# CD2840ADX-V2_2.net
KiCad netlist of a schematic drawn in Altium Designer
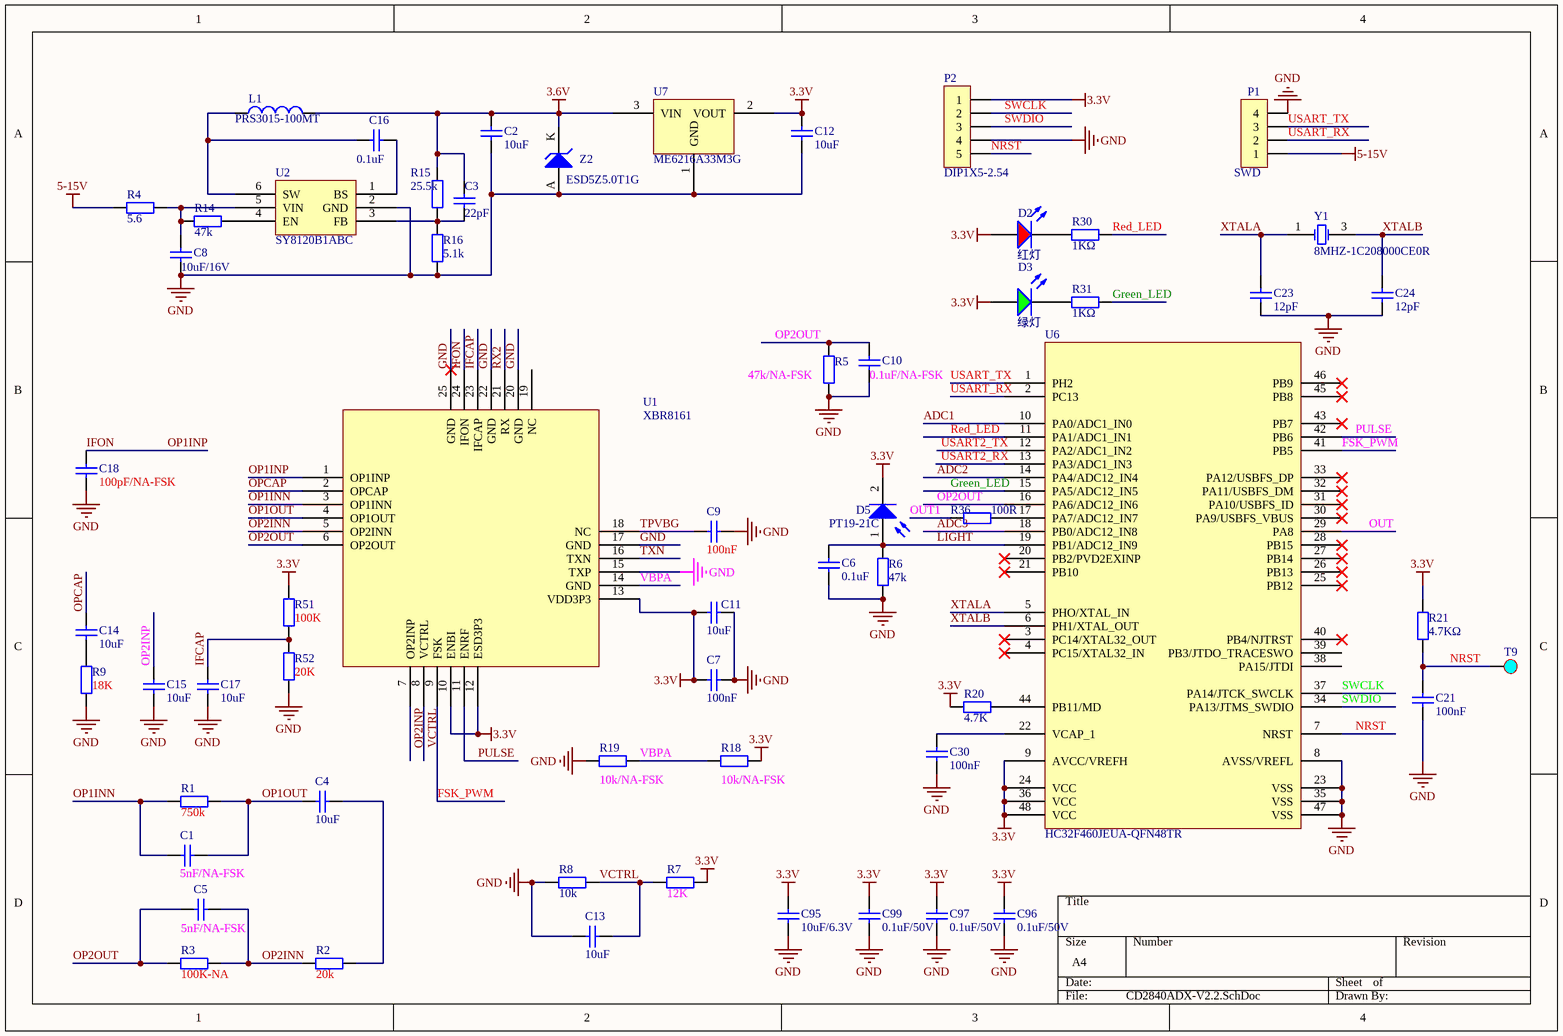
[diagram p0: CD2840ADX-V2.2.SchDoc]

(export (version "E")
  (design (tool "Eeschema 10.0.6"))
  (components
    (comp (ref "C1")
      (value "5nF/NA-FSK")
      (footprint "C0402")
      (description "Capacitor")
      (fields (field (name "PUBLISHER") "Altium Limited"))
      (libsource (lib "Miscellaneous Devices") (part "Cap"))
    )
    (comp (ref "C2")
      (value "10uF")
      (footprint "C0402")
      (description "Capacitor")
      (fields (field (name "PUBLISHER") "Altium Limited"))
      (libsource (lib "Miscellaneous Devices") (part "Cap"))
    )
    (comp (ref "C3")
      (value "22pF")
      (footprint "C0402")
      (description "Capacitor")
      (fields (field (name "PUBLISHER") "Altium Limited"))
      (libsource (lib "Miscellaneous Devices") (part "Cap"))
    )
    (comp (ref "C4")
      (value "10uF")
      (footprint "C0402")
      (description "Capacitor")
      (fields (field (name "PUBLISHER") "Altium Limited"))
      (libsource (lib "Miscellaneous Devices") (part "Cap"))
    )
    (comp (ref "C5")
      (value "5nF/NA-FSK")
      (footprint "C0402")
      (description "Capacitor")
      (fields (field (name "PUBLISHER") "Altium Limited"))
      (libsource (lib "Miscellaneous Devices") (part "Cap"))
    )
    (comp (ref "C6")
      (value "0.1uF")
      (footprint "C0402")
      (description "Capacitor")
      (fields (field (name "PUBLISHER") "Altium Limited"))
      (libsource (lib "Miscellaneous Devices") (part "Cap"))
    )
    (comp (ref "C7")
      (value "100nF")
      (footprint "C0402")
      (description "Capacitor")
      (fields (field (name "PUBLISHER") "Altium Limited"))
      (libsource (lib "Miscellaneous Devices") (part "Cap"))
    )
    (comp (ref "C8")
      (value "10uF/16V")
      (footprint "C0603")
      (description "Capacitor")
      (fields (field (name "PUBLISHER") "Altium Limited"))
      (libsource (lib "Miscellaneous Devices") (part "Cap"))
    )
    (comp (ref "C9")
      (value "100nF")
      (footprint "C0402")
      (description "Capacitor")
      (fields (field (name "PUBLISHER") "Altium Limited"))
      (libsource (lib "Miscellaneous Devices") (part "Cap"))
    )
    (comp (ref "C10")
      (value "0.1uF/NA-FSK")
      (footprint "C0402")
      (description "Capacitor")
      (fields (field (name "PUBLISHER") "Altium Limited"))
      (libsource (lib "Miscellaneous Devices") (part "Cap"))
    )
    (comp (ref "C11")
      (value "10uF")
      (footprint "C0402")
      (description "Capacitor")
      (fields (field (name "PUBLISHER") "Altium Limited"))
      (libsource (lib "Miscellaneous Devices") (part "Cap"))
    )
    (comp (ref "C12")
      (value "10uF")
      (footprint "C0402")
      (description "Capacitor")
      (fields (field (name "PUBLISHER") "Altium Limited"))
      (libsource (lib "Miscellaneous Devices") (part "Cap"))
    )
    (comp (ref "C13")
      (value "10uF")
      (footprint "C0402")
      (description "Capacitor")
      (fields (field (name "PUBLISHER") "Altium Limited"))
      (libsource (lib "Miscellaneous Devices") (part "Cap"))
    )
    (comp (ref "C14")
      (value "10uF")
      (footprint "C0402")
      (description "Capacitor")
      (fields (field (name "PUBLISHER") "Altium Limited"))
      (libsource (lib "Miscellaneous Devices") (part "Cap"))
    )
    (comp (ref "C15")
      (value "10uF")
      (footprint "C0402")
      (description "Capacitor")
      (fields (field (name "PUBLISHER") "Altium Limited"))
      (libsource (lib "Miscellaneous Devices") (part "Cap"))
    )
    (comp (ref "C16")
      (value "0.1uF")
      (footprint "C0402")
      (description "Capacitor")
      (fields (field (name "PUBLISHER") "Altium Limited"))
      (libsource (lib "Miscellaneous Devices") (part "Cap"))
    )
    (comp (ref "C17")
      (value "10uF")
      (footprint "C0402")
      (description "Capacitor")
      (fields (field (name "PUBLISHER") "Altium Limited"))
      (libsource (lib "Miscellaneous Devices") (part "Cap"))
    )
    (comp (ref "C18")
      (value "100pF/NA-FSK")
      (footprint "C0402")
      (description "Capacitor")
      (fields (field (name "PUBLISHER") "Altium Limited"))
      (libsource (lib "Miscellaneous Devices") (part "Cap"))
    )
    (comp (ref "C21")
      (value "100nF")
      (footprint "C0402")
      (description "贴片电容")
      (libsource (lib "Miscellaneous Devices LC") (part "0402 100nF (104) 10% 16V"))
    )
    (comp (ref "C23")
      (value "12pF")
      (footprint "C0402")
      (description "贴片电容")
      (libsource (lib "Cap") (part "0402 22pF (220) 5% 50V"))
    )
    (comp (ref "C24")
      (value "12pF")
      (footprint "C0402")
      (description "贴片电容")
      (libsource (lib "Cap") (part "0402 22pF (220) 5% 50V"))
    )
    (comp (ref "C30")
      (value "100nF")
      (footprint "C0402")
      (description "Capacitor")
      (fields (field (name "PUBLISHER") "Altium Limited"))
      (libsource (lib "Miscellaneous Devices") (part "Cap"))
    )
    (comp (ref "C95")
      (value "10uF/6.3V")
      (footprint "C0402")
      (description "贴片电容")
      (libsource (lib "Cap") (part "0402 2.2nF (222) 10% 50V"))
    )
    (comp (ref "C96")
      (value "0.1uF/50V")
      (footprint "C0402")
      (description "贴片电容")
      (libsource (lib "Cap") (part "0402 2.2nF (222) 10% 50V"))
    )
    (comp (ref "C97")
      (value "0.1uF/50V")
      (footprint "C0402")
      (description "贴片电容")
      (libsource (lib "Cap") (part "0402 2.2nF (222) 10% 50V"))
    )
    (comp (ref "C99")
      (value "0.1uF/50V")
      (footprint "C0402")
      (description "贴片电容")
      (libsource (lib "Cap") (part "0402 2.2nF (222) 10% 50V"))
    )
    (comp (ref "D2")
      (value "红灯")
      (footprint "LC-0603_LED_S1")
      (description "发光二极管")
      (libsource (lib "Miscellaneous Devices LC") (part "0603 红灯"))
    )
    (comp (ref "D3")
      (value "绿灯")
      (footprint "LC-0603_LED_S1")
      (description "发光二极管")
      (libsource (lib "30x35雷达微动底板V0.2") (part "0603 红灯"))
    )
    (comp (ref "D5")
      (value "PT19-21C")
      (footprint "LED-0603")
      (description "Photosensitive Diode")
      (fields (field (name "PUBLISHER") "Altium Limited"))
      (libsource (lib "Miscellaneous Devices") (part "Photo Sen"))
    )
    (comp (ref "L1")
      (value "PRS3015-100MT")
      (footprint "PRS3015")
      (description "Inductor")
      (fields (field (name "PUBLISHER") "Altium Limited"))
      (libsource (lib "Miscellaneous Devices") (part "Inductor"))
    )
    (comp (ref "P1")
      (value "SWD")
      (footprint "XH2.54mm")
      (description "4P接插件")
      (libsource (lib "STM32F407_CORE_BOARD") (part "Header 4"))
    )
    (comp (ref "P2")
      (value "DIP1X5-2.54")
      (footprint "DIP1X5-2.54")
      (description "4P接插件")
      (libsource (lib "CD2840ADX-V2.1") (part "Header 4"))
    )
    (comp (ref "R1")
      (value "750k")
      (footprint "R0402")
      (description "Resistor")
      (fields (field (name "PUBLISHER") "Altium Limited"))
      (libsource (lib "") (part "Res2_4"))
    )
    (comp (ref "R2")
      (value "20k")
      (footprint "R0402")
      (description "Resistor")
      (fields (field (name "PUBLISHER") "Altium Limited"))
      (libsource (lib "Miscellaneous Devices") (part "Res2"))
    )
    (comp (ref "R3")
      (value "100K-NA")
      (footprint "R0402")
      (description "Resistor")
      (fields (field (name "PUBLISHER") "Altium Limited"))
      (libsource (lib "Miscellaneous Devices") (part "Res2"))
    )
    (comp (ref "R4")
      (value "5.6")
      (footprint "R0402")
      (description "Resistor")
      (fields (field (name "PUBLISHER") "Altium Limited"))
      (libsource (lib "") (part "Res2_3"))
    )
    (comp (ref "R5")
      (value "47k/NA-FSK")
      (footprint "R0402")
      (description "Resistor")
      (fields (field (name "PUBLISHER") "Altium Limited"))
      (libsource (lib "") (part "Res2_1"))
    )
    (comp (ref "R6")
      (value "47k")
      (footprint "R0402")
      (description "Resistor")
      (fields (field (name "PUBLISHER") "Altium Limited"))
      (libsource (lib "") (part "Res2_1"))
    )
    (comp (ref "R7")
      (value "12K")
      (footprint "R0402")
      (description "Resistor")
      (fields (field (name "PUBLISHER") "Altium Limited"))
      (libsource (lib "Miscellaneous Devices") (part "Res2"))
    )
    (comp (ref "R8")
      (value "10k")
      (footprint "R0402")
      (description "Resistor")
      (fields (field (name "PUBLISHER") "Altium Limited"))
      (libsource (lib "Miscellaneous Devices") (part "Res2"))
    )
    (comp (ref "R9")
      (value "18K")
      (footprint "R0402")
      (description "Resistor")
      (fields (field (name "PUBLISHER") "Altium Limited"))
      (libsource (lib "") (part "Res2_1"))
    )
    (comp (ref "R14")
      (value "47k")
      (footprint "R0402")
      (description "Resistor")
      (fields (field (name "PUBLISHER") "Altium Limited"))
      (libsource (lib "Miscellaneous Devices") (part "Res2"))
    )
    (comp (ref "R15")
      (value "25.5k")
      (footprint "R0402")
      (description "Resistor")
      (fields (field (name "PUBLISHER") "Altium Limited"))
      (libsource (lib "") (part "Res2_2"))
    )
    (comp (ref "R16")
      (value "5.1k")
      (footprint "R0402")
      (description "Resistor")
      (fields (field (name "PUBLISHER") "Altium Limited"))
      (libsource (lib "") (part "Res2_2"))
    )
    (comp (ref "R18")
      (value "10k/NA-FSK")
      (footprint "R0402")
      (description "Resistor")
      (fields (field (name "PUBLISHER") "Altium Limited"))
      (libsource (lib "Miscellaneous Devices") (part "Res2"))
    )
    (comp (ref "R19")
      (value "10k/NA-FSK")
      (footprint "R0402")
      (description "Resistor")
      (fields (field (name "PUBLISHER") "Altium Limited"))
      (libsource (lib "Miscellaneous Devices") (part "Res2"))
    )
    (comp (ref "R20")
      (value "4.7K")
      (footprint "R0402")
      (description "Resistor")
      (fields (field (name "PUBLISHER") "Altium Limited"))
      (libsource (lib "") (part "Res2_4"))
    )
    (comp (ref "R21")
      (value "4.7KΩ")
      (footprint "R0402")
      (description "贴片电阻")
      (libsource (lib "") (part "0402 4.7KΩ (4701) 1%_1"))
    )
    (comp (ref "R30")
      (value "1KΩ")
      (footprint "R0402")
      (description "贴片电阻")
      (libsource (lib "Miscellaneous Devices LC") (part "0402 1KΩ (1001) 1%"))
    )
    (comp (ref "R31")
      (value "1KΩ")
      (footprint "R0402")
      (description "贴片电阻")
      (libsource (lib "Miscellaneous Devices LC") (part "0402 1KΩ (1001) 1%"))
    )
    (comp (ref "R36")
      (value "100R")
      (footprint "R0402")
      (description "贴片电阻")
      (libsource (lib "Miscellaneous Devices LC") (part "0402 4.7KΩ (4701) 1%"))
    )
    (comp (ref "R51")
      (value "100K")
      (footprint "R0402")
      (description "Resistor")
      (fields (field (name "PUBLISHER") "Altium Limited"))
      (libsource (lib "") (part "Res2_1"))
    )
    (comp (ref "R52")
      (value "20K")
      (footprint "R0402")
      (description "Resistor")
      (fields (field (name "PUBLISHER") "Altium Limited"))
      (libsource (lib "") (part "Res2_1"))
    )
    (comp (ref "T9")
      (value "~")
      (footprint "TestPoints")
      (description "TestPoints")
      (libsource (lib "标准原理图库（特种板）") (part "TestPoints"))
    )
    (comp (ref "U1")
      (value "XBR8161")
      (footprint "QFN24")
      (libsource (lib "altium-import") (part "root_0_XBR8161_"))
    )
    (comp (ref "U2") (value "SY8120B1ABC") (footprint "SOT-23-6") (libsource (lib "Schlib1") (part "H9108")))
    (comp (ref "U6")
      (value "HC32F460JEUA-QFN48TR")
      (footprint "QFN48-5X5mm")
      (libsource (lib "LD-ShouShi-Module-V1.0") (part "HC32F460JETA-LQFP48"))
    )
    (comp (ref "U7")
      (value "ME6216A33M3G")
      (footprint "SOT-23-L")
      (libsource (lib "Schlib1") (part "SSP6206"))
    )
    (comp (ref "Y1")
      (value "8MHZ-1C208000CE0R")
      (footprint "OSC-SMD_3225")
      (description "贴片晶振")
      (libsource (lib "CrystalOscillator") (part "SMD-3225_4P  25MHZ 12PF 10PPM"))
    )
    (comp (ref "Z2")
      (value "ESD5Z5.0T1G")
      (footprint "SOD323")
      (description "Zener Diode")
      (fields (field (name "PUBLISHER") "Altium Limited"))
      (libsource (lib "Miscellaneous Devices") (part "D Zener"))
    )
  )
  (nets
    (net (code "1") (name "/ADC1") (class "Default")
      (node (ref "U6") (pin "10") (pinfunction "PA0/ADC1_IN0_10") (pintype "passive"))
    )
    (net (code "2") (name "/ADC2") (class "Default")
      (node (ref "U6") (pin "14") (pinfunction "PA4/ADC12_IN4_14") (pintype "passive"))
    )
    (net (code "3") (name "/ADC3") (class "Default")
      (node (ref "U6") (pin "18") (pinfunction "PB0/ADC12_IN8_18") (pintype "passive"))
    )
    (net (code "4") (name "/FSK_PWM") (class "Default")
      (node (ref "U1") (pin "9") (pinfunction "FSK_9") (pintype "passive"))
      (node (ref "U6") (pin "41") (pinfunction "PB5_41") (pintype "passive"))
    )
    (net (code "5") (name "/Green_LED") (class "Default")
      (node (ref "R31") (pin "1") (pinfunction "1_1") (pintype "passive"))
      (node (ref "U6") (pin "15") (pinfunction "PA5/ADC12_IN5_15") (pintype "passive"))
    )
    (net (code "6") (name "/IFCAP") (class "Default")
      (node (ref "C17") (pin "2") (pinfunction "2_2") (pintype "passive"))
      (node (ref "R51") (pin "2") (pinfunction "2_2") (pintype "passive"))
      (node (ref "R52") (pin "1") (pinfunction "1_1") (pintype "passive"))
      (node (ref "U1") (pin "23") (pinfunction "IFCAP_23") (pintype "passive"))
    )
    (net (code "7") (name "/IFON") (class "Default")
      (node (ref "C18") (pin "2") (pinfunction "2_2") (pintype "passive"))
      (node (ref "U1") (pin "1") (pinfunction "OP1INP_1") (pintype "passive"))
      (node (ref "U1") (pin "24") (pinfunction "IFON_24") (pintype "passive"))
    )
    (net (code "8") (name "/LIGHT") (class "Default")
      (node (ref "C6") (pin "1") (pinfunction "1_1") (pintype "passive"))
      (node (ref "D5") (pin "1") (pinfunction "A_1") (pintype "passive"))
      (node (ref "R6") (pin "1") (pinfunction "1_1") (pintype "passive"))
      (node (ref "U6") (pin "19") (pinfunction "PB1/ADC12_IN9_19") (pintype "passive"))
    )
    (net (code "9") (name "/NRST") (class "Default")
      (node (ref "C21") (pin "2") (pinfunction "2_2") (pintype "passive"))
      (node (ref "P2") (pin "5") (pinfunction "5_5") (pintype "passive"))
      (node (ref "R21") (pin "1") (pinfunction "1_1") (pintype "passive"))
      (node (ref "T9") (pin "1") (pinfunction "1_1") (pintype "passive"))
      (node (ref "U6") (pin "7") (pinfunction "NRST_7") (pintype "passive"))
    )
    (net (code "10") (name "/OP1INN") (class "Default")
      (node (ref "C1") (pin "2") (pinfunction "2_2") (pintype "passive"))
      (node (ref "R1") (pin "1") (pinfunction "1_1") (pintype "passive"))
      (node (ref "U1") (pin "3") (pinfunction "OP1INN_3") (pintype "passive"))
    )
    (net (code "11") (name "/OP1OUT") (class "Default")
      (node (ref "C1") (pin "1") (pinfunction "1_1") (pintype "passive"))
      (node (ref "C4") (pin "2") (pinfunction "2_2") (pintype "passive"))
      (node (ref "R1") (pin "2") (pinfunction "2_2") (pintype "passive"))
      (node (ref "U1") (pin "4") (pinfunction "OP1OUT_4") (pintype "passive"))
    )
    (net (code "12") (name "/OP2INN") (class "Default")
      (node (ref "C5") (pin "2") (pinfunction "2_2") (pintype "passive"))
      (node (ref "R2") (pin "2") (pinfunction "2_2") (pintype "passive"))
      (node (ref "R3") (pin "1") (pinfunction "1_1") (pintype "passive"))
      (node (ref "U1") (pin "5") (pinfunction "OP2INN_5") (pintype "passive"))
    )
    (net (code "13") (name "/OP2INP") (class "Default")
      (node (ref "C15") (pin "1") (pinfunction "1_1") (pintype "passive"))
      (node (ref "U1") (pin "7") (pinfunction "OP2INP_7") (pintype "passive"))
    )
    (net (code "14") (name "/OP2OUT") (class "Default")
      (node (ref "C10") (pin "1") (pinfunction "1_1") (pintype "passive"))
      (node (ref "C5") (pin "1") (pinfunction "1_1") (pintype "passive"))
      (node (ref "R3") (pin "2") (pinfunction "2_2") (pintype "passive"))
      (node (ref "R5") (pin "1") (pinfunction "1_1") (pintype "passive"))
      (node (ref "U1") (pin "6") (pinfunction "OP2OUT_6") (pintype "passive"))
      (node (ref "U6") (pin "16") (pinfunction "PA6/ADC12_IN6_16") (pintype "passive"))
    )
    (net (code "15") (name "/OPCAP") (class "Default")
      (node (ref "C14") (pin "2") (pinfunction "2_2") (pintype "passive"))
      (node (ref "U1") (pin "2") (pinfunction "OPCAP_2") (pintype "passive"))
    )
    (net (code "16") (name "/OUT") (class "Default")
      (node (ref "U6") (pin "29") (pinfunction "PA8_29") (pintype "passive"))
    )
    (net (code "17") (name "/OUT1") (class "Default")
      (node (ref "R36") (pin "2") (pinfunction "2_2") (pintype "passive"))
    )
    (net (code "18") (name "/PULSE") (class "Default")
      (node (ref "U1") (pin "11") (pinfunction "ENRF_11") (pintype "passive"))
      (node (ref "U6") (pin "42") (pinfunction "PB6_42") (pintype "passive"))
    )
    (net (code "19") (name "/RX2") (class "Default")
      (node (ref "U1") (pin "21") (pinfunction "RX_21") (pintype "passive"))
    )
    (net (code "20") (name "/Red_LED") (class "Default")
      (node (ref "R30") (pin "1") (pinfunction "1_1") (pintype "passive"))
      (node (ref "U6") (pin "11") (pinfunction "PA1/ADC1_IN1_11") (pintype "passive"))
    )
    (net (code "21") (name "/SWCLK") (class "Default")
      (node (ref "P2") (pin "2") (pinfunction "2_2") (pintype "passive"))
      (node (ref "U6") (pin "37") (pinfunction "PA14/JTCK_SWCLK_37") (pintype "passive"))
    )
    (net (code "22") (name "/SWDIO") (class "Default")
      (node (ref "P2") (pin "3") (pinfunction "3_3") (pintype "passive"))
      (node (ref "U6") (pin "34") (pinfunction "PA13/JTMS_SWDIO_34") (pintype "passive"))
    )
    (net (code "23") (name "/TPVBG") (class "Default")
      (node (ref "C9") (pin "2") (pinfunction "2_2") (pintype "passive"))
      (node (ref "U1") (pin "18") (pinfunction "NC_18") (pintype "passive"))
    )
    (net (code "24") (name "/TXN") (class "Default")
      (node (ref "U1") (pin "16") (pinfunction "TXN_16") (pintype "passive"))
    )
    (net (code "25") (name "/USART2_RX") (class "Default")
      (node (ref "U6") (pin "13") (pinfunction "PA3/ADC1_IN3_13") (pintype "passive"))
    )
    (net (code "26") (name "/USART2_TX") (class "Default")
      (node (ref "U6") (pin "12") (pinfunction "PA2/ADC1_IN2_12") (pintype "passive"))
    )
    (net (code "27") (name "/USART_RX") (class "Default")
      (node (ref "P1") (pin "2") (pinfunction "2_2") (pintype "passive"))
      (node (ref "U6") (pin "2") (pinfunction "PC13_2") (pintype "passive"))
    )
    (net (code "28") (name "/USART_TX") (class "Default")
      (node (ref "P1") (pin "3") (pinfunction "3_3") (pintype "passive"))
      (node (ref "U6") (pin "1") (pinfunction "PH2_1") (pintype "passive"))
    )
    (net (code "29") (name "/VBPA") (class "Default")
      (node (ref "R18") (pin "2") (pinfunction "2_2") (pintype "passive"))
      (node (ref "R19") (pin "1") (pinfunction "1_1") (pintype "passive"))
      (node (ref "U1") (pin "14") (pinfunction "GND_14") (pintype "passive"))
    )
    (net (code "30") (name "/VCTRL") (class "Default")
      (node (ref "C13") (pin "1") (pinfunction "1_1") (pintype "passive"))
      (node (ref "R7") (pin "2") (pinfunction "2_2") (pintype "passive"))
      (node (ref "R8") (pin "1") (pinfunction "1_1") (pintype "passive"))
      (node (ref "U1") (pin "8") (pinfunction "VCTRL_8") (pintype "passive"))
    )
    (net (code "31") (name "/XTALA") (class "Default")
      (node (ref "C23") (pin "2") (pinfunction "2_2") (pintype "passive"))
      (node (ref "U6") (pin "5") (pinfunction "PHO/XTAL_IN_5") (pintype "passive"))
      (node (ref "Y1") (pin "1") (pinfunction "OSC1_1") (pintype "passive"))
    )
    (net (code "32") (name "/XTALB") (class "Default")
      (node (ref "C24") (pin "2") (pinfunction "2_2") (pintype "passive"))
      (node (ref "U6") (pin "6") (pinfunction "PH1/XTAL_OUT_6") (pintype "passive"))
      (node (ref "Y1") (pin "3") (pinfunction "OSC2_3") (pintype "passive"))
    )
    (net (code "33") (name "3.3V") (class "Default")
      (node (ref "C11") (pin "2") (pinfunction "2_2") (pintype "passive"))
      (node (ref "C12") (pin "1") (pinfunction "1_1") (pintype "passive"))
      (node (ref "C7") (pin "2") (pinfunction "2_2") (pintype "passive"))
      (node (ref "C95") (pin "1") (pinfunction "1_1") (pintype "passive"))
      (node (ref "C96") (pin "1") (pinfunction "1_1") (pintype "passive"))
      (node (ref "C97") (pin "1") (pinfunction "1_1") (pintype "passive"))
      (node (ref "C99") (pin "1") (pinfunction "1_1") (pintype "passive"))
      (node (ref "D2") (pin "A") (pinfunction "A_A") (pintype "passive"))
      (node (ref "D3") (pin "A") (pinfunction "A_A") (pintype "passive"))
      (node (ref "D5") (pin "2") (pinfunction "K_2") (pintype "passive"))
      (node (ref "P2") (pin "1") (pinfunction "1_1") (pintype "passive"))
      (node (ref "R18") (pin "1") (pinfunction "1_1") (pintype "passive"))
      (node (ref "R20") (pin "1") (pinfunction "1_1") (pintype "passive"))
      (node (ref "R21") (pin "2") (pinfunction "2_2") (pintype "passive"))
      (node (ref "R51") (pin "1") (pinfunction "1_1") (pintype "passive"))
      (node (ref "R7") (pin "1") (pinfunction "1_1") (pintype "passive"))
      (node (ref "U1") (pin "10") (pinfunction "ENBI_10") (pintype "passive"))
      (node (ref "U1") (pin "12") (pinfunction "ESD3P3_12") (pintype "passive"))
      (node (ref "U1") (pin "13") (pinfunction "VDD3P3_13") (pintype "passive"))
      (node (ref "U6") (pin "24") (pinfunction "VCC_24") (pintype "passive"))
      (node (ref "U6") (pin "36") (pinfunction "VCC_36") (pintype "passive"))
      (node (ref "U6") (pin "48") (pinfunction "VCC_48") (pintype "passive"))
      (node (ref "U6") (pin "9") (pinfunction "AVCC/VREFH_9") (pintype "passive"))
      (node (ref "U7") (pin "2") (pinfunction "VOUT_2") (pintype "passive"))
    )
    (net (code "34") (name "3.6V") (class "Default")
      (node (ref "C2") (pin "1") (pinfunction "1_1") (pintype "passive"))
      (node (ref "C3") (pin "2") (pinfunction "2_2") (pintype "passive"))
      (node (ref "L1") (pin "2") (pinfunction "2_2") (pintype "passive"))
      (node (ref "R15") (pin "2") (pinfunction "2_2") (pintype "passive"))
      (node (ref "U7") (pin "3") (pinfunction "VIN_3") (pintype "passive"))
      (node (ref "Z2") (pin "K") (pinfunction "K_K") (pintype "passive"))
    )
    (net (code "35") (name "5-15V") (class "Default")
      (node (ref "P1") (pin "1") (pinfunction "1_1") (pintype "passive"))
      (node (ref "R4") (pin "1") (pinfunction "1_1") (pintype "passive"))
    )
    (net (code "36") (name "GND") (class "Default")
      (node (ref "C10") (pin "2") (pinfunction "2_2") (pintype "passive"))
      (node (ref "C11") (pin "1") (pinfunction "1_1") (pintype "passive"))
      (node (ref "C12") (pin "2") (pinfunction "2_2") (pintype "passive"))
      (node (ref "C13") (pin "2") (pinfunction "2_2") (pintype "passive"))
      (node (ref "C15") (pin "2") (pinfunction "2_2") (pintype "passive"))
      (node (ref "C17") (pin "1") (pinfunction "1_1") (pintype "passive"))
      (node (ref "C18") (pin "1") (pinfunction "1_1") (pintype "passive"))
      (node (ref "C2") (pin "2") (pinfunction "2_2") (pintype "passive"))
      (node (ref "C21") (pin "1") (pinfunction "1_1") (pintype "passive"))
      (node (ref "C23") (pin "1") (pinfunction "1_1") (pintype "passive"))
      (node (ref "C24") (pin "1") (pinfunction "1_1") (pintype "passive"))
      (node (ref "C30") (pin "2") (pinfunction "2_2") (pintype "passive"))
      (node (ref "C6") (pin "2") (pinfunction "2_2") (pintype "passive"))
      (node (ref "C7") (pin "1") (pinfunction "1_1") (pintype "passive"))
      (node (ref "C8") (pin "2") (pinfunction "2_2") (pintype "passive"))
      (node (ref "C9") (pin "1") (pinfunction "1_1") (pintype "passive"))
      (node (ref "C95") (pin "2") (pinfunction "2_2") (pintype "passive"))
      (node (ref "C96") (pin "2") (pinfunction "2_2") (pintype "passive"))
      (node (ref "C97") (pin "2") (pinfunction "2_2") (pintype "passive"))
      (node (ref "C99") (pin "2") (pinfunction "2_2") (pintype "passive"))
      (node (ref "P1") (pin "4") (pinfunction "4_4") (pintype "passive"))
      (node (ref "P2") (pin "4") (pinfunction "4_4") (pintype "passive"))
      (node (ref "R16") (pin "1") (pinfunction "1_1") (pintype "passive"))
      (node (ref "R19") (pin "2") (pinfunction "2_2") (pintype "passive"))
      (node (ref "R5") (pin "2") (pinfunction "2_2") (pintype "passive"))
      (node (ref "R52") (pin "2") (pinfunction "2_2") (pintype "passive"))
      (node (ref "R6") (pin "2") (pinfunction "2_2") (pintype "passive"))
      (node (ref "R8") (pin "2") (pinfunction "2_2") (pintype "passive"))
      (node (ref "R9") (pin "2") (pinfunction "2_2") (pintype "passive"))
      (node (ref "U1") (pin "15") (pinfunction "TXP_15") (pintype "passive"))
      (node (ref "U1") (pin "17") (pinfunction "GND_17") (pintype "passive"))
      (node (ref "U1") (pin "20") (pinfunction "GND_20") (pintype "passive"))
      (node (ref "U1") (pin "22") (pinfunction "GND_22") (pintype "passive"))
      (node (ref "U1") (pin "25") (pinfunction "GND_25") (pintype "passive"))
      (node (ref "U2") (pin "2") (pinfunction "GND_2") (pintype "passive"))
      (node (ref "U6") (pin "23") (pinfunction "VSS_23") (pintype "passive"))
      (node (ref "U6") (pin "35") (pinfunction "VSS_35") (pintype "passive"))
      (node (ref "U6") (pin "47") (pinfunction "VSS_47") (pintype "passive"))
      (node (ref "U6") (pin "8") (pinfunction "AVSS/VREFL_8") (pintype "passive"))
      (node (ref "U7") (pin "1") (pinfunction "GND_1") (pintype "passive"))
      (node (ref "Z2") (pin "A") (pinfunction "A_A") (pintype "passive"))
    )
    (net (code "37") (name "Net-(C4-Pad1)") (class "Default")
      (node (ref "C4") (pin "1") (pinfunction "1_1") (pintype "passive"))
      (node (ref "R2") (pin "1") (pinfunction "1_1") (pintype "passive"))
    )
    (net (code "38") (name "Net-(C14-Pad1)") (class "Default")
      (node (ref "C14") (pin "1") (pinfunction "1_1") (pintype "passive"))
      (node (ref "R9") (pin "1") (pinfunction "1_1") (pintype "passive"))
    )
    (net (code "39") (name "Net-(D2-PadK)") (class "Default")
      (node (ref "D2") (pin "K") (pinfunction "K_K") (pintype "passive"))
      (node (ref "R30") (pin "2") (pinfunction "2_2") (pintype "passive"))
    )
    (net (code "40") (name "Net-(D3-PadK)") (class "Default")
      (node (ref "D3") (pin "K") (pinfunction "K_K") (pintype "passive"))
      (node (ref "R31") (pin "2") (pinfunction "2_2") (pintype "passive"))
    )
    (net (code "41") (name "Net-(U2-BS)") (class "Default")
      (node (ref "C16") (pin "2") (pinfunction "2_2") (pintype "passive"))
      (node (ref "U2") (pin "1") (pinfunction "BS_1") (pintype "passive"))
    )
    (net (code "42") (name "Net-(U2-EN)") (class "Default")
      (node (ref "R14") (pin "1") (pinfunction "1_1") (pintype "passive"))
      (node (ref "U2") (pin "4") (pinfunction "EN_4") (pintype "passive"))
    )
    (net (code "43") (name "Net-(U2-FB)") (class "Default")
      (node (ref "C3") (pin "1") (pinfunction "1_1") (pintype "passive"))
      (node (ref "R15") (pin "1") (pinfunction "1_1") (pintype "passive"))
      (node (ref "R16") (pin "2") (pinfunction "2_2") (pintype "passive"))
      (node (ref "U2") (pin "3") (pinfunction "FB_3") (pintype "passive"))
    )
    (net (code "44") (name "Net-(U2-SW)") (class "Default")
      (node (ref "C16") (pin "1") (pinfunction "1_1") (pintype "passive"))
      (node (ref "L1") (pin "1") (pinfunction "1_1") (pintype "passive"))
      (node (ref "U2") (pin "6") (pinfunction "SW_6") (pintype "passive"))
    )
    (net (code "45") (name "Net-(U2-VIN)") (class "Default")
      (node (ref "C8") (pin "1") (pinfunction "1_1") (pintype "passive"))
      (node (ref "R14") (pin "2") (pinfunction "2_2") (pintype "passive"))
      (node (ref "R4") (pin "2") (pinfunction "2_2") (pintype "passive"))
      (node (ref "U2") (pin "5") (pinfunction "VIN_5") (pintype "passive"))
    )
    (net (code "46") (name "Net-(U6-PA7{slash}ADC12_IN7)") (class "Default")
      (node (ref "R36") (pin "1") (pinfunction "1_1") (pintype "passive"))
      (node (ref "U6") (pin "17") (pinfunction "PA7/ADC12_IN7_17") (pintype "passive"))
    )
    (net (code "47") (name "Net-(U6-PB11{slash}MD)") (class "Default")
      (node (ref "R20") (pin "2") (pinfunction "2_2") (pintype "passive"))
      (node (ref "U6") (pin "44") (pinfunction "PB11/MD_44") (pintype "passive"))
    )
    (net (code "48") (name "Net-(U6-VCAP_1)") (class "Default")
      (node (ref "C30") (pin "1") (pinfunction "1_1") (pintype "passive"))
      (node (ref "U6") (pin "22") (pinfunction "VCAP_1_22") (pintype "passive"))
    )
    (net (code "49") (name "unconnected-(U1-NC-Pad19)") (class "Default")
      (node (ref "U1") (pin "19") (pinfunction "NC_19") (pintype "passive"))
    )
    (net (code "50") (name "unconnected-(U6-PA9{slash}USBFS_VBUS-Pad30)") (class "Default")
      (node (ref "U6") (pin "30") (pinfunction "PA9/USBFS_VBUS_30") (pintype "passive+no_connect"))
    )
    (net (code "51") (name "unconnected-(U6-PA10{slash}USBFS_ID-Pad31)") (class "Default")
      (node (ref "U6") (pin "31") (pinfunction "PA10/USBFS_ID_31") (pintype "passive+no_connect"))
    )
    (net (code "52") (name "unconnected-(U6-PA11{slash}USBFS_DM-Pad32)") (class "Default")
      (node (ref "U6") (pin "32") (pinfunction "PA11/USBFS_DM_32") (pintype "passive+no_connect"))
    )
    (net (code "53") (name "unconnected-(U6-PA12{slash}USBFS_DP-Pad33)") (class "Default")
      (node (ref "U6") (pin "33") (pinfunction "PA12/USBFS_DP_33") (pintype "passive+no_connect"))
    )
    (net (code "54") (name "unconnected-(U6-PA15{slash}JTDI-Pad38)") (class "Default")
      (node (ref "U6") (pin "38") (pinfunction "PA15/JTDI_38") (pintype "passive"))
    )
    (net (code "55") (name "unconnected-(U6-PB2{slash}PVD2EXINP-Pad20)") (class "Default")
      (node (ref "U6") (pin "20") (pinfunction "PB2/PVD2EXINP_20") (pintype "passive+no_connect"))
    )
    (net (code "56") (name "unconnected-(U6-PB3{slash}JTDO_TRACESWO-Pad39)") (class "Default")
      (node (ref "U6") (pin "39") (pinfunction "PB3/JTDO_TRACESWO_39") (pintype "passive"))
    )
    (net (code "57") (name "unconnected-(U6-PB4{slash}NJTRST-Pad40)") (class "Default")
      (node (ref "U6") (pin "40") (pinfunction "PB4/NJTRST_40") (pintype "passive+no_connect"))
    )
    (net (code "58") (name "unconnected-(U6-PB7-Pad43)") (class "Default")
      (node (ref "U6") (pin "43") (pinfunction "PB7_43") (pintype "passive+no_connect"))
    )
    (net (code "59") (name "unconnected-(U6-PB8-Pad45)") (class "Default")
      (node (ref "U6") (pin "45") (pinfunction "PB8_45") (pintype "passive+no_connect"))
    )
    (net (code "60") (name "unconnected-(U6-PB9-Pad46)") (class "Default")
      (node (ref "U6") (pin "46") (pinfunction "PB9_46") (pintype "passive+no_connect"))
    )
    (net (code "61") (name "unconnected-(U6-PB10-Pad21)") (class "Default")
      (node (ref "U6") (pin "21") (pinfunction "PB10_21") (pintype "passive+no_connect"))
    )
    (net (code "62") (name "unconnected-(U6-PB12-Pad25)") (class "Default")
      (node (ref "U6") (pin "25") (pinfunction "PB12_25") (pintype "passive+no_connect"))
    )
    (net (code "63") (name "unconnected-(U6-PB13-Pad26)") (class "Default")
      (node (ref "U6") (pin "26") (pinfunction "PB13_26") (pintype "passive+no_connect"))
    )
    (net (code "64") (name "unconnected-(U6-PB14-Pad27)") (class "Default")
      (node (ref "U6") (pin "27") (pinfunction "PB14_27") (pintype "passive+no_connect"))
    )
    (net (code "65") (name "unconnected-(U6-PB15-Pad28)") (class "Default")
      (node (ref "U6") (pin "28") (pinfunction "PB15_28") (pintype "passive+no_connect"))
    )
    (net (code "66") (name "unconnected-(U6-PC14{slash}XTAL32_OUT-Pad3)") (class "Default")
      (node (ref "U6") (pin "3") (pinfunction "PC14/XTAL32_OUT_3") (pintype "passive+no_connect"))
    )
    (net (code "67") (name "unconnected-(U6-PC15{slash}XTAL32_IN-Pad4)") (class "Default")
      (node (ref "U6") (pin "4") (pinfunction "PC15/XTAL32_IN_4") (pintype "passive+no_connect"))
    )
  )
)
